# schematic.net
KiCad netlist of a schematic drawn in EAGLE
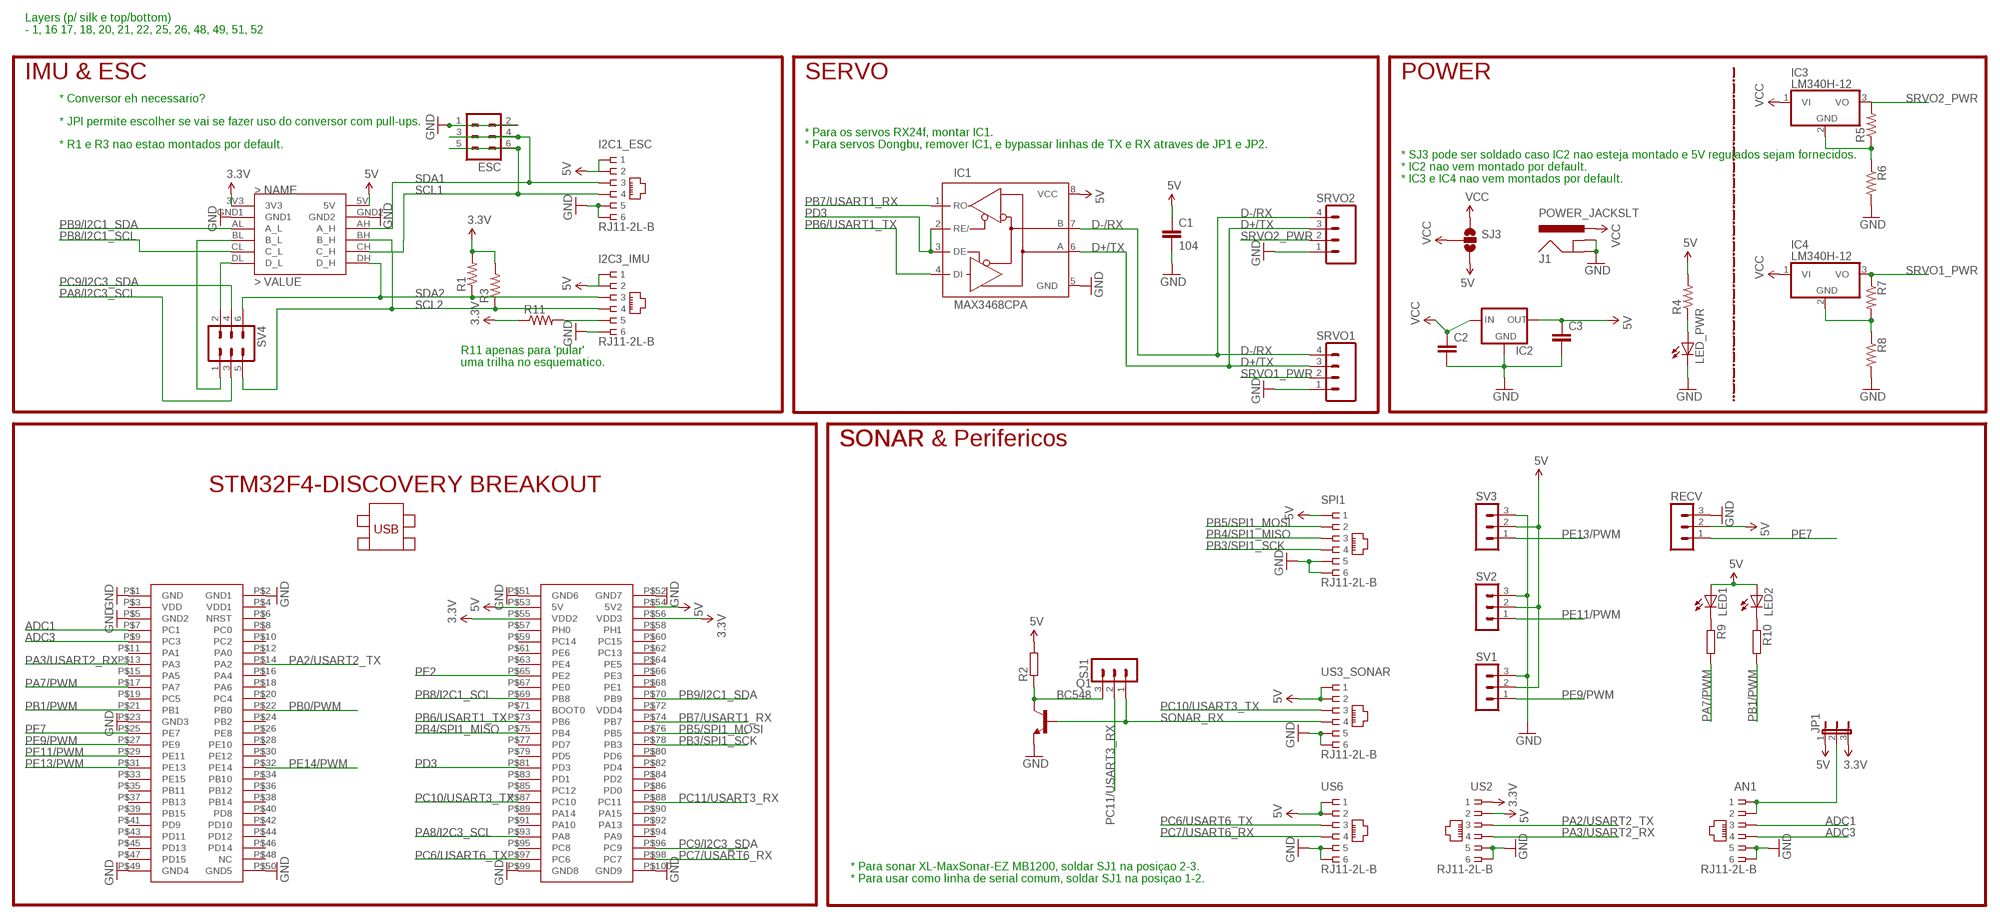
[diagram p0: schematic, sheet 1]

(export (version "E")
  (design (tool "Eeschema 10.0.6"))
  (components
    (comp (ref "AN1")
      (value "RJ11-2L-B")
      (footprint "eagle-import:RJ11-NO_SHIELD")
      (fields (field (name "MF") "TYCO ELECTRONICS"))
      (libsource (lib "eagle-import") (part "RJ11-2L-B"))
    )
    (comp (ref "C1")
      (value "104")
      (footprint "eagle-import:CAP-PTH-SMALL-KIT")
      (libsource (lib "eagle-import") (part "0.1UF-50V-20%(PTH)KIT-EZ"))
    )
    (comp (ref "C2")
      (value "C7.5/3")
      (footprint "eagle-import:C7.5B3")
      (libsource (lib "eagle-import") (part "C7.5/3"))
    )
    (comp (ref "C3")
      (value "0.1UF-50V-20%(PTH)KIT-EZ")
      (footprint "eagle-import:CAP-PTH-SMALL-KIT")
      (libsource (lib "eagle-import") (part "0.1UF-50V-20%(PTH)KIT-EZ"))
    )
    (comp (ref "ESC")
      (value "MA03-2")
      (footprint "eagle-import:MA03-2")
      (libsource (lib "eagle-import") (part "MA03-2"))
    )
    (comp (ref "I2C1_ESC")
      (value "RJ11-2L-B")
      (footprint "eagle-import:RJ11-NO_SHIELD")
      (fields (field (name "MF") "TYCO ELECTRONICS"))
      (libsource (lib "eagle-import") (part "RJ11-2L-B"))
    )
    (comp (ref "I2C3_IMU")
      (value "RJ11-2L-B")
      (footprint "eagle-import:RJ11-NO_SHIELD")
      (fields (field (name "MF") "TYCO ELECTRONICS"))
      (libsource (lib "eagle-import") (part "RJ11-2L-B"))
    )
    (comp (ref "IC1")
      (value "MAX3468CPA")
      (footprint "eagle-import:DIL08")
      (libsource (lib "eagle-import") (part "MAX34PA68C"))
    )
    (comp (ref "IC2")
      (value "V_REG_78XX-TO-220")
      (footprint "eagle-import:TO-220-ALT")
      (libsource (lib "eagle-import") (part "V_REG_78XX-TO-220"))
    )
    (comp (ref "IC3")
      (value "LM340H-12")
      (footprint "eagle-import:TO220H")
      (libsource (lib "eagle-import") (part "LM340?-H12"))
    )
    (comp (ref "IC4")
      (value "LM340H-12")
      (footprint "eagle-import:TO220H")
      (libsource (lib "eagle-import") (part "LM340?-H12"))
    )
    (comp (ref "J1")
      (value "POWER_JACKSLT")
      (footprint "eagle-import:POWER_JACK_SLOT")
      (libsource (lib "eagle-import") (part "POWER_JACKSLT"))
    )
    (comp (ref "JP1")
      (value "JP2E")
      (footprint "eagle-import:JP2")
      (libsource (lib "eagle-import") (part "JP2E"))
    )
    (comp (ref "LED1")
      (value "LED3MM")
      (footprint "eagle-import:LED3MM")
      (libsource (lib "eagle-import") (part "LED3MM"))
    )
    (comp (ref "LED2")
      (value "LED3MM")
      (footprint "eagle-import:LED3MM")
      (libsource (lib "eagle-import") (part "LED3MM"))
    )
    (comp (ref "LED_PWR")
      (value "LED5MM")
      (footprint "eagle-import:LED5MM")
      (libsource (lib "eagle-import") (part "LED5MM"))
    )
    (comp (ref "Q1")
      (value "BC548")
      (footprint "eagle-import:TO92-EBC")
      (libsource (lib "eagle-import") (part "BC548"))
    )
    (comp (ref "R1")
      (value "R-US_0204/5")
      (footprint "eagle-import:0204_5")
      (libsource (lib "eagle-import") (part "R-US_0204/5"))
    )
    (comp (ref "R2")
      (value "R-EU_0204/7")
      (footprint "eagle-import:0204_7")
      (libsource (lib "eagle-import") (part "R-EU_0204/7"))
    )
    (comp (ref "R3")
      (value "R-US_0204/5")
      (footprint "eagle-import:0204_5")
      (libsource (lib "eagle-import") (part "R-US_0204/5"))
    )
    (comp (ref "R4")
      (value "R-US_0204/7")
      (footprint "eagle-import:0204_7")
      (libsource (lib "eagle-import") (part "R-US_0204/7"))
    )
    (comp (ref "R5")
      (value "R-US_0204/7")
      (footprint "eagle-import:0204_7")
      (libsource (lib "eagle-import") (part "R-US_0204/7"))
    )
    (comp (ref "R6")
      (value "R-US_0204/7")
      (footprint "eagle-import:0204_7")
      (libsource (lib "eagle-import") (part "R-US_0204/7"))
    )
    (comp (ref "R7")
      (value "R-US_0204/7")
      (footprint "eagle-import:0204_7")
      (libsource (lib "eagle-import") (part "R-US_0204/7"))
    )
    (comp (ref "R8")
      (value "R-US_0204/7")
      (footprint "eagle-import:0204_7")
      (libsource (lib "eagle-import") (part "R-US_0204/7"))
    )
    (comp (ref "R9")
      (value "R-EU_0204/2V")
      (footprint "eagle-import:0204V")
      (libsource (lib "eagle-import") (part "R-EU_0204/2V"))
    )
    (comp (ref "R10")
      (value "R-EU_0204/2V")
      (footprint "eagle-import:0204V")
      (libsource (lib "eagle-import") (part "R-EU_0204/2V"))
    )
    (comp (ref "R11")
      (value "R-US_M1406")
      (footprint "eagle-import:M1406")
      (libsource (lib "eagle-import") (part "R-US_M1406"))
    )
    (comp (ref "RECV")
      (value "MA03-1")
      (footprint "eagle-import:MA03-1")
      (libsource (lib "eagle-import") (part "MA03-1"))
    )
    (comp (ref "SJ1")
      (value "MA03-1")
      (footprint "eagle-import:MA03-1")
      (libsource (lib "eagle-import") (part "MA03-1"))
    )
    (comp (ref "SJ3")
      (value "SOLDERJUMPER_2WAY-OLDW")
      (footprint "eagle-import:SJ_2W")
      (libsource (lib "eagle-import") (part "SOLDERJUMPER_2WAY-OLDW"))
    )
    (comp (ref "SPI1")
      (value "RJ11-2L-B")
      (footprint "eagle-import:RJ11-NO_SHIELD")
      (fields (field (name "MF") "TYCO ELECTRONICS"))
      (libsource (lib "eagle-import") (part "RJ11-2L-B"))
    )
    (comp (ref "SRVO1")
      (value "M04POLAR")
      (footprint "eagle-import:MOLEX-1X4")
      (libsource (lib "eagle-import") (part "M04POLAR"))
    )
    (comp (ref "SRVO2")
      (value "M04POLAR")
      (footprint "eagle-import:MOLEX-1X4")
      (libsource (lib "eagle-import") (part "M04POLAR"))
    )
    (comp (ref "SV1")
      (value "MA03-1")
      (footprint "eagle-import:MA03-1")
      (libsource (lib "eagle-import") (part "MA03-1"))
    )
    (comp (ref "SV2")
      (value "MA03-1")
      (footprint "eagle-import:MA03-1")
      (libsource (lib "eagle-import") (part "MA03-1"))
    )
    (comp (ref "SV3")
      (value "MA03-1")
      (footprint "eagle-import:MA03-1")
      (libsource (lib "eagle-import") (part "MA03-1"))
    )
    (comp (ref "SV4")
      (value "MA03-2")
      (footprint "eagle-import:MA03-2")
      (libsource (lib "eagle-import") (part "MA03-2"))
    )
    (comp (ref "U$1")
      (value "STM32F4-DISCOVERY")
      (footprint "eagle-import:STM32F4-DISCOVERY")
      (libsource (lib "eagle-import") (part "STM32F4-DISCOVERY"))
    )
    (comp (ref "U$2")
      (value "JYMCU_LOGIC_LEVEL_CONVERTER")
      (footprint "eagle-import:JYMCU_LOGIC_LEVEL_SHIFTER_DIP")
      (libsource (lib "eagle-import") (part "JYMCU_LOGIC_LEVEL_CONVERTER"))
    )
    (comp (ref "US2")
      (value "RJ11-2L-B")
      (footprint "eagle-import:RJ11-NO_SHIELD")
      (fields (field (name "MF") "TYCO ELECTRONICS"))
      (libsource (lib "eagle-import") (part "RJ11-2L-B"))
    )
    (comp (ref "US3_SONAR")
      (value "RJ11-2L-B")
      (footprint "eagle-import:RJ11-NO_SHIELD")
      (fields (field (name "MF") "TYCO ELECTRONICS"))
      (libsource (lib "eagle-import") (part "RJ11-2L-B"))
    )
    (comp (ref "US6")
      (value "RJ11-2L-B")
      (footprint "eagle-import:RJ11-NO_SHIELD")
      (fields (field (name "MF") "TYCO ELECTRONICS"))
      (libsource (lib "eagle-import") (part "RJ11-2L-B"))
    )
  )
  (nets
    (net (code "1") (name "/ADC1") (class "Default")
      (node (ref "AN1") (pin "3") (pinfunction "3_3") (pintype "passive"))
      (node (ref "U$1") (pin "P$7") (pinfunction "PC1_P$7") (pintype "bidirectional"))
    )
    (net (code "2") (name "/ADC3") (class "Default")
      (node (ref "AN1") (pin "4") (pinfunction "4_4") (pintype "passive"))
      (node (ref "U$1") (pin "P$9") (pinfunction "PC3_P$9") (pintype "bidirectional"))
    )
    (net (code "3") (name "/D+{slash}TX") (class "Default")
      (node (ref "IC1") (pin "6") (pinfunction "A_6") (pintype "passive"))
      (node (ref "SRVO1") (pin "3") (pinfunction "3_3") (pintype "passive"))
      (node (ref "SRVO2") (pin "3") (pinfunction "3_3") (pintype "passive"))
    )
    (net (code "4") (name "/D-{slash}RX") (class "Default")
      (node (ref "IC1") (pin "7") (pinfunction "B_7") (pintype "passive"))
      (node (ref "SRVO1") (pin "4") (pinfunction "4_4") (pintype "passive"))
      (node (ref "SRVO2") (pin "4") (pinfunction "4_4") (pintype "passive"))
    )
    (net (code "5") (name "/PA2{slash}USART2_TX") (class "Default")
      (node (ref "U$1") (pin "P$14") (pinfunction "PA2_P$14") (pintype "bidirectional"))
      (node (ref "US2") (pin "3") (pinfunction "3_3") (pintype "passive"))
    )
    (net (code "6") (name "/PA3{slash}USART2_RX") (class "Default")
      (node (ref "U$1") (pin "P$13") (pinfunction "PA3_P$13") (pintype "bidirectional"))
      (node (ref "US2") (pin "4") (pinfunction "4_4") (pintype "passive"))
    )
    (net (code "7") (name "/PA7{slash}PWM") (class "Default")
      (node (ref "R9") (pin "2") (pinfunction "2_2") (pintype "passive"))
      (node (ref "U$1") (pin "P$17") (pinfunction "PA7_P$17") (pintype "bidirectional"))
    )
    (net (code "8") (name "/PA8{slash}I2C3_SCL") (class "Default")
      (node (ref "SV4") (pin "3") (pinfunction "3_3") (pintype "passive"))
      (node (ref "U$1") (pin "P$93") (pinfunction "PA8_P$93") (pintype "bidirectional"))
    )
    (net (code "9") (name "/PB0{slash}PWM") (class "Default")
      (node (ref "U$1") (pin "P$22") (pinfunction "PB0_P$22") (pintype "bidirectional"))
    )
    (net (code "10") (name "/PB1{slash}PWM") (class "Default")
      (node (ref "R10") (pin "2") (pinfunction "2_2") (pintype "passive"))
      (node (ref "U$1") (pin "P$21") (pinfunction "PB1_P$21") (pintype "bidirectional"))
    )
    (net (code "11") (name "/PB3{slash}SPI1_SCK") (class "Default")
      (node (ref "SPI1") (pin "4") (pinfunction "4_4") (pintype "passive"))
      (node (ref "U$1") (pin "P$78") (pinfunction "PB3_P$78") (pintype "bidirectional"))
    )
    (net (code "12") (name "/PB4{slash}SPI1_MISO") (class "Default")
      (node (ref "SPI1") (pin "3") (pinfunction "3_3") (pintype "passive"))
      (node (ref "U$1") (pin "P$75") (pinfunction "PB4_P$75") (pintype "bidirectional"))
    )
    (net (code "13") (name "/PB5{slash}SPI1_MOSI") (class "Default")
      (node (ref "SPI1") (pin "2") (pinfunction "2_2") (pintype "passive"))
      (node (ref "U$1") (pin "P$76") (pinfunction "PB5_P$76") (pintype "bidirectional"))
    )
    (net (code "14") (name "/PB6{slash}USART1_TX") (class "Default")
      (node (ref "IC1") (pin "4") (pinfunction "DI_4") (pintype "input"))
      (node (ref "U$1") (pin "P$73") (pinfunction "PB6_P$73") (pintype "bidirectional"))
    )
    (net (code "15") (name "/PB7{slash}USART1_RX") (class "Default")
      (node (ref "IC1") (pin "1") (pinfunction "RO_1") (pintype "output"))
      (node (ref "U$1") (pin "P$74") (pinfunction "PB7_P$74") (pintype "bidirectional"))
    )
    (net (code "16") (name "/PB8{slash}I2C1_SCL") (class "Default")
      (node (ref "U$1") (pin "P$69") (pinfunction "PB8_P$69") (pintype "bidirectional"))
      (node (ref "U$2") (pin "CL") (pinfunction "C_L_CL") (pintype "bidirectional"))
    )
    (net (code "17") (name "/PB9{slash}I2C1_SDA") (class "Default")
      (node (ref "U$1") (pin "P$70") (pinfunction "PB9_P$70") (pintype "bidirectional"))
      (node (ref "U$2") (pin "AL") (pinfunction "A_L_AL") (pintype "bidirectional"))
    )
    (net (code "18") (name "/PC6{slash}USART6_TX") (class "Default")
      (node (ref "U$1") (pin "P$97") (pinfunction "PC6_P$97") (pintype "bidirectional"))
      (node (ref "US6") (pin "3") (pinfunction "3_3") (pintype "passive"))
    )
    (net (code "19") (name "/PC7{slash}USART6_RX") (class "Default")
      (node (ref "U$1") (pin "P$98") (pinfunction "PC7_P$98") (pintype "bidirectional"))
      (node (ref "US6") (pin "4") (pinfunction "4_4") (pintype "passive"))
    )
    (net (code "20") (name "/PC9{slash}I2C3_SDA") (class "Default")
      (node (ref "SV4") (pin "4") (pinfunction "4_4") (pintype "passive"))
      (node (ref "U$1") (pin "P$96") (pinfunction "PC9_P$96") (pintype "bidirectional"))
    )
    (net (code "21") (name "/PC10{slash}USART3_TX") (class "Default")
      (node (ref "U$1") (pin "P$87") (pinfunction "PC10_P$87") (pintype "bidirectional"))
      (node (ref "US3_SONAR") (pin "3") (pinfunction "3_3") (pintype "passive"))
    )
    (net (code "22") (name "/PC11{slash}USART3_RX") (class "Default")
      (node (ref "SJ1") (pin "2") (pinfunction "2_2") (pintype "passive"))
      (node (ref "U$1") (pin "P$88") (pinfunction "PC11_P$88") (pintype "bidirectional"))
    )
    (net (code "23") (name "/PD3") (class "Default")
      (node (ref "IC1") (pin "2") (pinfunction "RE/_2") (pintype "input"))
      (node (ref "IC1") (pin "3") (pinfunction "DE_3") (pintype "input"))
      (node (ref "U$1") (pin "P$81") (pinfunction "PD3_P$81") (pintype "bidirectional"))
    )
    (net (code "24") (name "/PE2") (class "Default")
      (node (ref "U$1") (pin "P$65") (pinfunction "PE2_P$65") (pintype "bidirectional"))
    )
    (net (code "25") (name "/PE7") (class "Default")
      (node (ref "RECV") (pin "1") (pinfunction "1_1") (pintype "passive"))
      (node (ref "U$1") (pin "P$25") (pinfunction "PE7_P$25") (pintype "bidirectional"))
    )
    (net (code "26") (name "/PE9{slash}PWM") (class "Default")
      (node (ref "SV1") (pin "1") (pinfunction "1_1") (pintype "passive"))
      (node (ref "U$1") (pin "P$27") (pinfunction "PE9_P$27") (pintype "bidirectional"))
    )
    (net (code "27") (name "/PE11{slash}PWM") (class "Default")
      (node (ref "SV2") (pin "1") (pinfunction "1_1") (pintype "passive"))
      (node (ref "U$1") (pin "P$29") (pinfunction "PE11_P$29") (pintype "bidirectional"))
    )
    (net (code "28") (name "/PE13{slash}PWM") (class "Default")
      (node (ref "SV3") (pin "1") (pinfunction "1_1") (pintype "passive"))
      (node (ref "U$1") (pin "P$31") (pinfunction "PE13_P$31") (pintype "bidirectional"))
    )
    (net (code "29") (name "/PE14{slash}PWM") (class "Default")
      (node (ref "U$1") (pin "P$32") (pinfunction "PE14_P$32") (pintype "bidirectional"))
    )
    (net (code "30") (name "/SCL1") (class "Default")
      (node (ref "ESC") (pin "5") (pinfunction "5_5") (pintype "passive"))
      (node (ref "ESC") (pin "6") (pinfunction "6_6") (pintype "passive"))
      (node (ref "I2C1_ESC") (pin "4") (pinfunction "4_4") (pintype "passive"))
      (node (ref "U$2") (pin "CH") (pinfunction "C_H_CH") (pintype "bidirectional"))
    )
    (net (code "31") (name "/SCL2") (class "Default")
      (node (ref "I2C3_IMU") (pin "4") (pinfunction "4_4") (pintype "passive"))
      (node (ref "R3") (pin "1") (pinfunction "1_1") (pintype "passive"))
      (node (ref "SV4") (pin "5") (pinfunction "5_5") (pintype "passive"))
      (node (ref "U$2") (pin "BH") (pinfunction "B_H_BH") (pintype "bidirectional"))
    )
    (net (code "32") (name "/SDA1") (class "Default")
      (node (ref "ESC") (pin "3") (pinfunction "3_3") (pintype "passive"))
      (node (ref "ESC") (pin "4") (pinfunction "4_4") (pintype "passive"))
      (node (ref "I2C1_ESC") (pin "3") (pinfunction "3_3") (pintype "passive"))
      (node (ref "U$2") (pin "AH") (pinfunction "A_H_AH") (pintype "bidirectional"))
    )
    (net (code "33") (name "/SDA2") (class "Default")
      (node (ref "I2C3_IMU") (pin "3") (pinfunction "3_3") (pintype "passive"))
      (node (ref "R1") (pin "1") (pinfunction "1_1") (pintype "passive"))
      (node (ref "SV4") (pin "6") (pinfunction "6_6") (pintype "passive"))
      (node (ref "U$2") (pin "DH") (pinfunction "D_H_DH") (pintype "bidirectional"))
    )
    (net (code "34") (name "/SONAR_RX") (class "Default")
      (node (ref "Q1") (pin "B") (pinfunction "B_B") (pintype "passive"))
      (node (ref "SJ1") (pin "1") (pinfunction "1_1") (pintype "passive"))
      (node (ref "US3_SONAR") (pin "4") (pinfunction "4_4") (pintype "passive"))
    )
    (net (code "35") (name "/SRVO1_PWR") (class "Default")
      (node (ref "IC4") (pin "3") (pinfunction "VO_3") (pintype "passive"))
      (node (ref "R7") (pin "1") (pinfunction "1_1") (pintype "passive"))
      (node (ref "SRVO1") (pin "2") (pinfunction "2_2") (pintype "passive"))
    )
    (net (code "36") (name "/SRVO2_PWR") (class "Default")
      (node (ref "IC3") (pin "3") (pinfunction "VO_3") (pintype "passive"))
      (node (ref "R5") (pin "2") (pinfunction "2_2") (pintype "passive"))
      (node (ref "SRVO2") (pin "2") (pinfunction "2_2") (pintype "passive"))
    )
    (net (code "37") (name "3.3V") (class "Default")
      (node (ref "JP1") (pin "3") (pinfunction "3_3") (pintype "passive"))
      (node (ref "R1") (pin "2") (pinfunction "2_2") (pintype "passive"))
      (node (ref "R11") (pin "1") (pinfunction "1_1") (pintype "passive"))
      (node (ref "R3") (pin "2") (pinfunction "2_2") (pintype "passive"))
      (node (ref "U$1") (pin "P$55") (pinfunction "VDD2_P$55") (pintype "bidirectional"))
      (node (ref "U$1") (pin "P$56") (pinfunction "VDD3_P$56") (pintype "bidirectional"))
      (node (ref "U$2") (pin "3V3") (pinfunction "3V3_3V3") (pintype "bidirectional"))
      (node (ref "US2") (pin "1") (pinfunction "1_1") (pintype "passive"))
    )
    (net (code "38") (name "5V") (class "Default")
      (node (ref "C1") (pin "1") (pinfunction "1_1") (pintype "passive"))
      (node (ref "C3") (pin "1") (pinfunction "1_1") (pintype "passive"))
      (node (ref "I2C1_ESC") (pin "1") (pinfunction "1_1") (pintype "passive"))
      (node (ref "I2C1_ESC") (pin "2") (pinfunction "2_2") (pintype "passive"))
      (node (ref "I2C3_IMU") (pin "1") (pinfunction "1_1") (pintype "passive"))
      (node (ref "I2C3_IMU") (pin "2") (pinfunction "2_2") (pintype "passive"))
      (node (ref "IC1") (pin "8") (pinfunction "VCC_8") (pintype "power_in"))
      (node (ref "IC2") (pin "OUT") (pinfunction "OUT_OUT") (pintype "output"))
      (node (ref "JP1") (pin "1") (pinfunction "1_1") (pintype "passive"))
      (node (ref "LED1") (pin "A") (pinfunction "A_A") (pintype "passive"))
      (node (ref "LED2") (pin "A") (pinfunction "A_A") (pintype "passive"))
      (node (ref "R2") (pin "2") (pinfunction "2_2") (pintype "passive"))
      (node (ref "R4") (pin "2") (pinfunction "2_2") (pintype "passive"))
      (node (ref "RECV") (pin "2") (pinfunction "2_2") (pintype "passive"))
      (node (ref "SJ3") (pin "3") (pinfunction "3_3") (pintype "passive"))
      (node (ref "SPI1") (pin "1") (pinfunction "1_1") (pintype "passive"))
      (node (ref "SV1") (pin "2") (pinfunction "2_2") (pintype "passive"))
      (node (ref "SV2") (pin "2") (pinfunction "2_2") (pintype "passive"))
      (node (ref "SV3") (pin "2") (pinfunction "2_2") (pintype "passive"))
      (node (ref "U$1") (pin "P$53") (pinfunction "5V_P$53") (pintype "bidirectional"))
      (node (ref "U$1") (pin "P$54") (pinfunction "5V2_P$54") (pintype "bidirectional"))
      (node (ref "U$2") (pin "5V") (pinfunction "5V_5V") (pintype "bidirectional"))
      (node (ref "US2") (pin "2") (pinfunction "2_2") (pintype "passive"))
      (node (ref "US3_SONAR") (pin "1") (pinfunction "1_1") (pintype "passive"))
      (node (ref "US3_SONAR") (pin "2") (pinfunction "2_2") (pintype "passive"))
      (node (ref "US6") (pin "1") (pinfunction "1_1") (pintype "passive"))
      (node (ref "US6") (pin "2") (pinfunction "2_2") (pintype "passive"))
    )
    (net (code "39") (name "GND") (class "Default")
      (node (ref "AN1") (pin "5") (pinfunction "5_5") (pintype "passive"))
      (node (ref "AN1") (pin "6") (pinfunction "6_6") (pintype "passive"))
      (node (ref "C1") (pin "2") (pinfunction "2_2") (pintype "passive"))
      (node (ref "C2") (pin "2") (pinfunction "2_2") (pintype "passive"))
      (node (ref "C3") (pin "2") (pinfunction "2_2") (pintype "passive"))
      (node (ref "ESC") (pin "1") (pinfunction "1_1") (pintype "passive"))
      (node (ref "ESC") (pin "2") (pinfunction "2_2") (pintype "passive"))
      (node (ref "I2C1_ESC") (pin "5") (pinfunction "5_5") (pintype "passive"))
      (node (ref "I2C1_ESC") (pin "6") (pinfunction "6_6") (pintype "passive"))
      (node (ref "I2C3_IMU") (pin "6") (pinfunction "6_6") (pintype "passive"))
      (node (ref "IC1") (pin "5") (pinfunction "GND_5") (pintype "power_in"))
      (node (ref "IC2") (pin "GND") (pinfunction "GND_GND") (pintype "input"))
      (node (ref "J1") (pin "GND@1") (pinfunction "GNDBREAK_GND@1") (pintype "bidirectional"))
      (node (ref "J1") (pin "GND@2") (pinfunction "GND_GND@2") (pintype "bidirectional"))
      (node (ref "LED_PWR") (pin "K") (pinfunction "C_K") (pintype "passive"))
      (node (ref "Q1") (pin "E") (pinfunction "E_E") (pintype "passive"))
      (node (ref "R6") (pin "2") (pinfunction "2_2") (pintype "passive"))
      (node (ref "R8") (pin "2") (pinfunction "2_2") (pintype "passive"))
      (node (ref "RECV") (pin "3") (pinfunction "3_3") (pintype "passive"))
      (node (ref "SPI1") (pin "5") (pinfunction "5_5") (pintype "passive"))
      (node (ref "SPI1") (pin "6") (pinfunction "6_6") (pintype "passive"))
      (node (ref "SRVO1") (pin "1") (pinfunction "1_1") (pintype "passive"))
      (node (ref "SRVO2") (pin "1") (pinfunction "1_1") (pintype "passive"))
      (node (ref "SV1") (pin "3") (pinfunction "3_3") (pintype "passive"))
      (node (ref "SV2") (pin "3") (pinfunction "3_3") (pintype "passive"))
      (node (ref "SV3") (pin "3") (pinfunction "3_3") (pintype "passive"))
      (node (ref "U$1") (pin "P$1") (pinfunction "GND_P$1") (pintype "bidirectional"))
      (node (ref "U$1") (pin "P$100") (pinfunction "GND9_P$100") (pintype "bidirectional"))
      (node (ref "U$1") (pin "P$2") (pinfunction "GND1_P$2") (pintype "bidirectional"))
      (node (ref "U$1") (pin "P$23") (pinfunction "GND3_P$23") (pintype "bidirectional"))
      (node (ref "U$1") (pin "P$49") (pinfunction "GND4_P$49") (pintype "bidirectional"))
      (node (ref "U$1") (pin "P$5") (pinfunction "GND2_P$5") (pintype "bidirectional"))
      (node (ref "U$1") (pin "P$50") (pinfunction "GND5_P$50") (pintype "bidirectional"))
      (node (ref "U$1") (pin "P$51") (pinfunction "GND6_P$51") (pintype "bidirectional"))
      (node (ref "U$1") (pin "P$52") (pinfunction "GND7_P$52") (pintype "bidirectional"))
      (node (ref "U$1") (pin "P$99") (pinfunction "GND8_P$99") (pintype "bidirectional"))
      (node (ref "U$2") (pin "GND1") (pinfunction "GND1_GND1") (pintype "bidirectional"))
      (node (ref "U$2") (pin "GND2") (pinfunction "GND2_GND2") (pintype "bidirectional"))
      (node (ref "US2") (pin "5") (pinfunction "5_5") (pintype "passive"))
      (node (ref "US2") (pin "6") (pinfunction "6_6") (pintype "passive"))
      (node (ref "US3_SONAR") (pin "5") (pinfunction "5_5") (pintype "passive"))
      (node (ref "US3_SONAR") (pin "6") (pinfunction "6_6") (pintype "passive"))
      (node (ref "US6") (pin "5") (pinfunction "5_5") (pintype "passive"))
      (node (ref "US6") (pin "6") (pinfunction "6_6") (pintype "passive"))
    )
    (net (code "40") (name "Net-(AN1-Pad1)") (class "Default")
      (node (ref "AN1") (pin "1") (pinfunction "1_1") (pintype "passive"))
      (node (ref "AN1") (pin "2") (pinfunction "2_2") (pintype "passive"))
      (node (ref "JP1") (pin "2") (pinfunction "2_2") (pintype "passive"))
    )
    (net (code "41") (name "Net-(I2C3_IMU-Pad5)") (class "Default")
      (node (ref "I2C3_IMU") (pin "5") (pinfunction "5_5") (pintype "passive"))
      (node (ref "R11") (pin "2") (pinfunction "2_2") (pintype "passive"))
    )
    (net (code "42") (name "Net-(IC3-GND)") (class "Default")
      (node (ref "IC3") (pin "2") (pinfunction "GND_2") (pintype "passive"))
      (node (ref "R5") (pin "1") (pinfunction "1_1") (pintype "passive"))
      (node (ref "R6") (pin "1") (pinfunction "1_1") (pintype "passive"))
    )
    (net (code "43") (name "Net-(IC4-GND)") (class "Default")
      (node (ref "IC4") (pin "2") (pinfunction "GND_2") (pintype "passive"))
      (node (ref "R7") (pin "2") (pinfunction "2_2") (pintype "passive"))
      (node (ref "R8") (pin "1") (pinfunction "1_1") (pintype "passive"))
    )
    (net (code "44") (name "Net-(LED1-C)") (class "Default")
      (node (ref "LED1") (pin "K") (pinfunction "C_K") (pintype "passive"))
      (node (ref "R9") (pin "1") (pinfunction "1_1") (pintype "passive"))
    )
    (net (code "45") (name "Net-(LED2-C)") (class "Default")
      (node (ref "LED2") (pin "K") (pinfunction "C_K") (pintype "passive"))
      (node (ref "R10") (pin "1") (pinfunction "1_1") (pintype "passive"))
    )
    (net (code "46") (name "Net-(LED_PWR-PadA)") (class "Default")
      (node (ref "LED_PWR") (pin "A") (pinfunction "A_A") (pintype "passive"))
      (node (ref "R4") (pin "1") (pinfunction "1_1") (pintype "passive"))
    )
    (net (code "47") (name "Net-(Q1-PadC)") (class "Default")
      (node (ref "Q1") (pin "C") (pinfunction "C_C") (pintype "passive"))
      (node (ref "R2") (pin "1") (pinfunction "1_1") (pintype "passive"))
      (node (ref "SJ1") (pin "3") (pinfunction "3_3") (pintype "passive"))
    )
    (net (code "48") (name "Net-(U$2-B_L)") (class "Default")
      (node (ref "SV4") (pin "1") (pinfunction "1_1") (pintype "passive"))
      (node (ref "U$2") (pin "BL") (pinfunction "B_L_BL") (pintype "bidirectional"))
    )
    (net (code "49") (name "Net-(U$2-D_L)") (class "Default")
      (node (ref "SV4") (pin "2") (pinfunction "2_2") (pintype "passive"))
      (node (ref "U$2") (pin "DL") (pinfunction "D_L_DL") (pintype "bidirectional"))
    )
    (net (code "50") (name "VCC") (class "Default")
      (node (ref "C2") (pin "1") (pinfunction "1_1") (pintype "passive"))
      (node (ref "IC2") (pin "IN") (pinfunction "IN_IN") (pintype "input"))
      (node (ref "IC3") (pin "1") (pinfunction "VI_1") (pintype "input"))
      (node (ref "IC4") (pin "1") (pinfunction "VI_1") (pintype "input"))
      (node (ref "J1") (pin "PWR") (pinfunction "PWR_PWR") (pintype "bidirectional"))
      (node (ref "SJ3") (pin "1") (pinfunction "1_1") (pintype "passive"))
      (node (ref "SJ3") (pin "2") (pinfunction "2_2") (pintype "passive"))
    )
    (net (code "51") (name "unconnected-(U$1-BOOT0-PadP$71)") (class "Default")
      (node (ref "U$1") (pin "P$71") (pinfunction "BOOT0_P$71") (pintype "bidirectional"))
    )
    (net (code "52") (name "unconnected-(U$1-NC-PadP$48)") (class "Default")
      (node (ref "U$1") (pin "P$48") (pinfunction "NC_P$48") (pintype "bidirectional"))
    )
    (net (code "53") (name "unconnected-(U$1-NRST-PadP$6)") (class "Default")
      (node (ref "U$1") (pin "P$6") (pinfunction "NRST_P$6") (pintype "bidirectional"))
    )
    (net (code "54") (name "unconnected-(U$1-PA0-PadP$12)") (class "Default")
      (node (ref "U$1") (pin "P$12") (pinfunction "PA0_P$12") (pintype "bidirectional"))
    )
    (net (code "55") (name "unconnected-(U$1-PA1-PadP$11)") (class "Default")
      (node (ref "U$1") (pin "P$11") (pinfunction "PA1_P$11") (pintype "bidirectional"))
    )
    (net (code "56") (name "unconnected-(U$1-PA4-PadP$16)") (class "Default")
      (node (ref "U$1") (pin "P$16") (pinfunction "PA4_P$16") (pintype "bidirectional"))
    )
    (net (code "57") (name "unconnected-(U$1-PA5-PadP$15)") (class "Default")
      (node (ref "U$1") (pin "P$15") (pinfunction "PA5_P$15") (pintype "bidirectional"))
    )
    (net (code "58") (name "unconnected-(U$1-PA6-PadP$18)") (class "Default")
      (node (ref "U$1") (pin "P$18") (pinfunction "PA6_P$18") (pintype "bidirectional"))
    )
    (net (code "59") (name "unconnected-(U$1-PA9-PadP$94)") (class "Default")
      (node (ref "U$1") (pin "P$94") (pinfunction "PA9_P$94") (pintype "bidirectional"))
    )
    (net (code "60") (name "unconnected-(U$1-PA10-PadP$91)") (class "Default")
      (node (ref "U$1") (pin "P$91") (pinfunction "PA10_P$91") (pintype "bidirectional"))
    )
    (net (code "61") (name "unconnected-(U$1-PA13-PadP$92)") (class "Default")
      (node (ref "U$1") (pin "P$92") (pinfunction "PA13_P$92") (pintype "bidirectional"))
    )
    (net (code "62") (name "unconnected-(U$1-PA14-PadP$89)") (class "Default")
      (node (ref "U$1") (pin "P$89") (pinfunction "PA14_P$89") (pintype "bidirectional"))
    )
    (net (code "63") (name "unconnected-(U$1-PA15-PadP$90)") (class "Default")
      (node (ref "U$1") (pin "P$90") (pinfunction "PA15_P$90") (pintype "bidirectional"))
    )
    (net (code "64") (name "unconnected-(U$1-PB2-PadP$24)") (class "Default")
      (node (ref "U$1") (pin "P$24") (pinfunction "PB2_P$24") (pintype "bidirectional"))
    )
    (net (code "65") (name "unconnected-(U$1-PB10-PadP$34)") (class "Default")
      (node (ref "U$1") (pin "P$34") (pinfunction "PB10_P$34") (pintype "bidirectional"))
    )
    (net (code "66") (name "unconnected-(U$1-PB11-PadP$35)") (class "Default")
      (node (ref "U$1") (pin "P$35") (pinfunction "PB11_P$35") (pintype "bidirectional"))
    )
    (net (code "67") (name "unconnected-(U$1-PB12-PadP$36)") (class "Default")
      (node (ref "U$1") (pin "P$36") (pinfunction "PB12_P$36") (pintype "bidirectional"))
    )
    (net (code "68") (name "unconnected-(U$1-PB13-PadP$37)") (class "Default")
      (node (ref "U$1") (pin "P$37") (pinfunction "PB13_P$37") (pintype "bidirectional"))
    )
    (net (code "69") (name "unconnected-(U$1-PB14-PadP$38)") (class "Default")
      (node (ref "U$1") (pin "P$38") (pinfunction "PB14_P$38") (pintype "bidirectional"))
    )
    (net (code "70") (name "unconnected-(U$1-PB15-PadP$39)") (class "Default")
      (node (ref "U$1") (pin "P$39") (pinfunction "PB15_P$39") (pintype "bidirectional"))
    )
    (net (code "71") (name "unconnected-(U$1-PC0-PadP$8)") (class "Default")
      (node (ref "U$1") (pin "P$8") (pinfunction "PC0_P$8") (pintype "bidirectional"))
    )
    (net (code "72") (name "unconnected-(U$1-PC2-PadP$10)") (class "Default")
      (node (ref "U$1") (pin "P$10") (pinfunction "PC2_P$10") (pintype "bidirectional"))
    )
    (net (code "73") (name "unconnected-(U$1-PC4-PadP$20)") (class "Default")
      (node (ref "U$1") (pin "P$20") (pinfunction "PC4_P$20") (pintype "bidirectional"))
    )
    (net (code "74") (name "unconnected-(U$1-PC5-PadP$19)") (class "Default")
      (node (ref "U$1") (pin "P$19") (pinfunction "PC5_P$19") (pintype "bidirectional"))
    )
    (net (code "75") (name "unconnected-(U$1-PC8-PadP$95)") (class "Default")
      (node (ref "U$1") (pin "P$95") (pinfunction "PC8_P$95") (pintype "bidirectional"))
    )
    (net (code "76") (name "unconnected-(U$1-PC12-PadP$85)") (class "Default")
      (node (ref "U$1") (pin "P$85") (pinfunction "PC12_P$85") (pintype "bidirectional"))
    )
    (net (code "77") (name "unconnected-(U$1-PC13-PadP$62)") (class "Default")
      (node (ref "U$1") (pin "P$62") (pinfunction "PC13_P$62") (pintype "bidirectional"))
    )
    (net (code "78") (name "unconnected-(U$1-PC14-PadP$59)") (class "Default")
      (node (ref "U$1") (pin "P$59") (pinfunction "PC14_P$59") (pintype "bidirectional"))
    )
    (net (code "79") (name "unconnected-(U$1-PC15-PadP$60)") (class "Default")
      (node (ref "U$1") (pin "P$60") (pinfunction "PC15_P$60") (pintype "bidirectional"))
    )
    (net (code "80") (name "unconnected-(U$1-PD0-PadP$86)") (class "Default")
      (node (ref "U$1") (pin "P$86") (pinfunction "PD0_P$86") (pintype "bidirectional"))
    )
    (net (code "81") (name "unconnected-(U$1-PD1-PadP$83)") (class "Default")
      (node (ref "U$1") (pin "P$83") (pinfunction "PD1_P$83") (pintype "bidirectional"))
    )
    (net (code "82") (name "unconnected-(U$1-PD2-PadP$84)") (class "Default")
      (node (ref "U$1") (pin "P$84") (pinfunction "PD2_P$84") (pintype "bidirectional"))
    )
    (net (code "83") (name "unconnected-(U$1-PD4-PadP$82)") (class "Default")
      (node (ref "U$1") (pin "P$82") (pinfunction "PD4_P$82") (pintype "bidirectional"))
    )
    (net (code "84") (name "unconnected-(U$1-PD5-PadP$79)") (class "Default")
      (node (ref "U$1") (pin "P$79") (pinfunction "PD5_P$79") (pintype "bidirectional"))
    )
    (net (code "85") (name "unconnected-(U$1-PD6-PadP$80)") (class "Default")
      (node (ref "U$1") (pin "P$80") (pinfunction "PD6_P$80") (pintype "bidirectional"))
    )
    (net (code "86") (name "unconnected-(U$1-PD7-PadP$77)") (class "Default")
      (node (ref "U$1") (pin "P$77") (pinfunction "PD7_P$77") (pintype "bidirectional"))
    )
    (net (code "87") (name "unconnected-(U$1-PD8-PadP$40)") (class "Default")
      (node (ref "U$1") (pin "P$40") (pinfunction "PD8_P$40") (pintype "bidirectional"))
    )
    (net (code "88") (name "unconnected-(U$1-PD9-PadP$41)") (class "Default")
      (node (ref "U$1") (pin "P$41") (pinfunction "PD9_P$41") (pintype "bidirectional"))
    )
    (net (code "89") (name "unconnected-(U$1-PD10-PadP$42)") (class "Default")
      (node (ref "U$1") (pin "P$42") (pinfunction "PD10_P$42") (pintype "bidirectional"))
    )
    (net (code "90") (name "unconnected-(U$1-PD11-PadP$43)") (class "Default")
      (node (ref "U$1") (pin "P$43") (pinfunction "PD11_P$43") (pintype "bidirectional"))
    )
    (net (code "91") (name "unconnected-(U$1-PD12-PadP$44)") (class "Default")
      (node (ref "U$1") (pin "P$44") (pinfunction "PD12_P$44") (pintype "bidirectional"))
    )
    (net (code "92") (name "unconnected-(U$1-PD13-PadP$45)") (class "Default")
      (node (ref "U$1") (pin "P$45") (pinfunction "PD13_P$45") (pintype "bidirectional"))
    )
    (net (code "93") (name "unconnected-(U$1-PD14-PadP$46)") (class "Default")
      (node (ref "U$1") (pin "P$46") (pinfunction "PD14_P$46") (pintype "bidirectional"))
    )
    (net (code "94") (name "unconnected-(U$1-PD15-PadP$47)") (class "Default")
      (node (ref "U$1") (pin "P$47") (pinfunction "PD15_P$47") (pintype "bidirectional"))
    )
    (net (code "95") (name "unconnected-(U$1-PE0-PadP$67)") (class "Default")
      (node (ref "U$1") (pin "P$67") (pinfunction "PE0_P$67") (pintype "bidirectional"))
    )
    (net (code "96") (name "unconnected-(U$1-PE1-PadP$68)") (class "Default")
      (node (ref "U$1") (pin "P$68") (pinfunction "PE1_P$68") (pintype "bidirectional"))
    )
    (net (code "97") (name "unconnected-(U$1-PE3-PadP$66)") (class "Default")
      (node (ref "U$1") (pin "P$66") (pinfunction "PE3_P$66") (pintype "bidirectional"))
    )
    (net (code "98") (name "unconnected-(U$1-PE4-PadP$63)") (class "Default")
      (node (ref "U$1") (pin "P$63") (pinfunction "PE4_P$63") (pintype "bidirectional"))
    )
    (net (code "99") (name "unconnected-(U$1-PE5-PadP$64)") (class "Default")
      (node (ref "U$1") (pin "P$64") (pinfunction "PE5_P$64") (pintype "bidirectional"))
    )
    (net (code "100") (name "unconnected-(U$1-PE6-PadP$61)") (class "Default")
      (node (ref "U$1") (pin "P$61") (pinfunction "PE6_P$61") (pintype "bidirectional"))
    )
    (net (code "101") (name "unconnected-(U$1-PE8-PadP$26)") (class "Default")
      (node (ref "U$1") (pin "P$26") (pinfunction "PE8_P$26") (pintype "bidirectional"))
    )
    (net (code "102") (name "unconnected-(U$1-PE10-PadP$28)") (class "Default")
      (node (ref "U$1") (pin "P$28") (pinfunction "PE10_P$28") (pintype "bidirectional"))
    )
    (net (code "103") (name "unconnected-(U$1-PE12-PadP$30)") (class "Default")
      (node (ref "U$1") (pin "P$30") (pinfunction "PE12_P$30") (pintype "bidirectional"))
    )
    (net (code "104") (name "unconnected-(U$1-PE15-PadP$33)") (class "Default")
      (node (ref "U$1") (pin "P$33") (pinfunction "PE15_P$33") (pintype "bidirectional"))
    )
    (net (code "105") (name "unconnected-(U$1-PH0-PadP$57)") (class "Default")
      (node (ref "U$1") (pin "P$57") (pinfunction "PH0_P$57") (pintype "bidirectional"))
    )
    (net (code "106") (name "unconnected-(U$1-PH1-PadP$58)") (class "Default")
      (node (ref "U$1") (pin "P$58") (pinfunction "PH1_P$58") (pintype "bidirectional"))
    )
    (net (code "107") (name "unconnected-(U$1-VDD-PadP$3)") (class "Default")
      (node (ref "U$1") (pin "P$3") (pinfunction "VDD_P$3") (pintype "bidirectional"))
    )
    (net (code "108") (name "unconnected-(U$1-VDD1-PadP$4)") (class "Default")
      (node (ref "U$1") (pin "P$4") (pinfunction "VDD1_P$4") (pintype "bidirectional"))
    )
    (net (code "109") (name "unconnected-(U$1-VDD4-PadP$72)") (class "Default")
      (node (ref "U$1") (pin "P$72") (pinfunction "VDD4_P$72") (pintype "bidirectional"))
    )
  )
)
